# TaSCUD_ver03.net
KiCad netlist of a schematic drawn in EAGLE
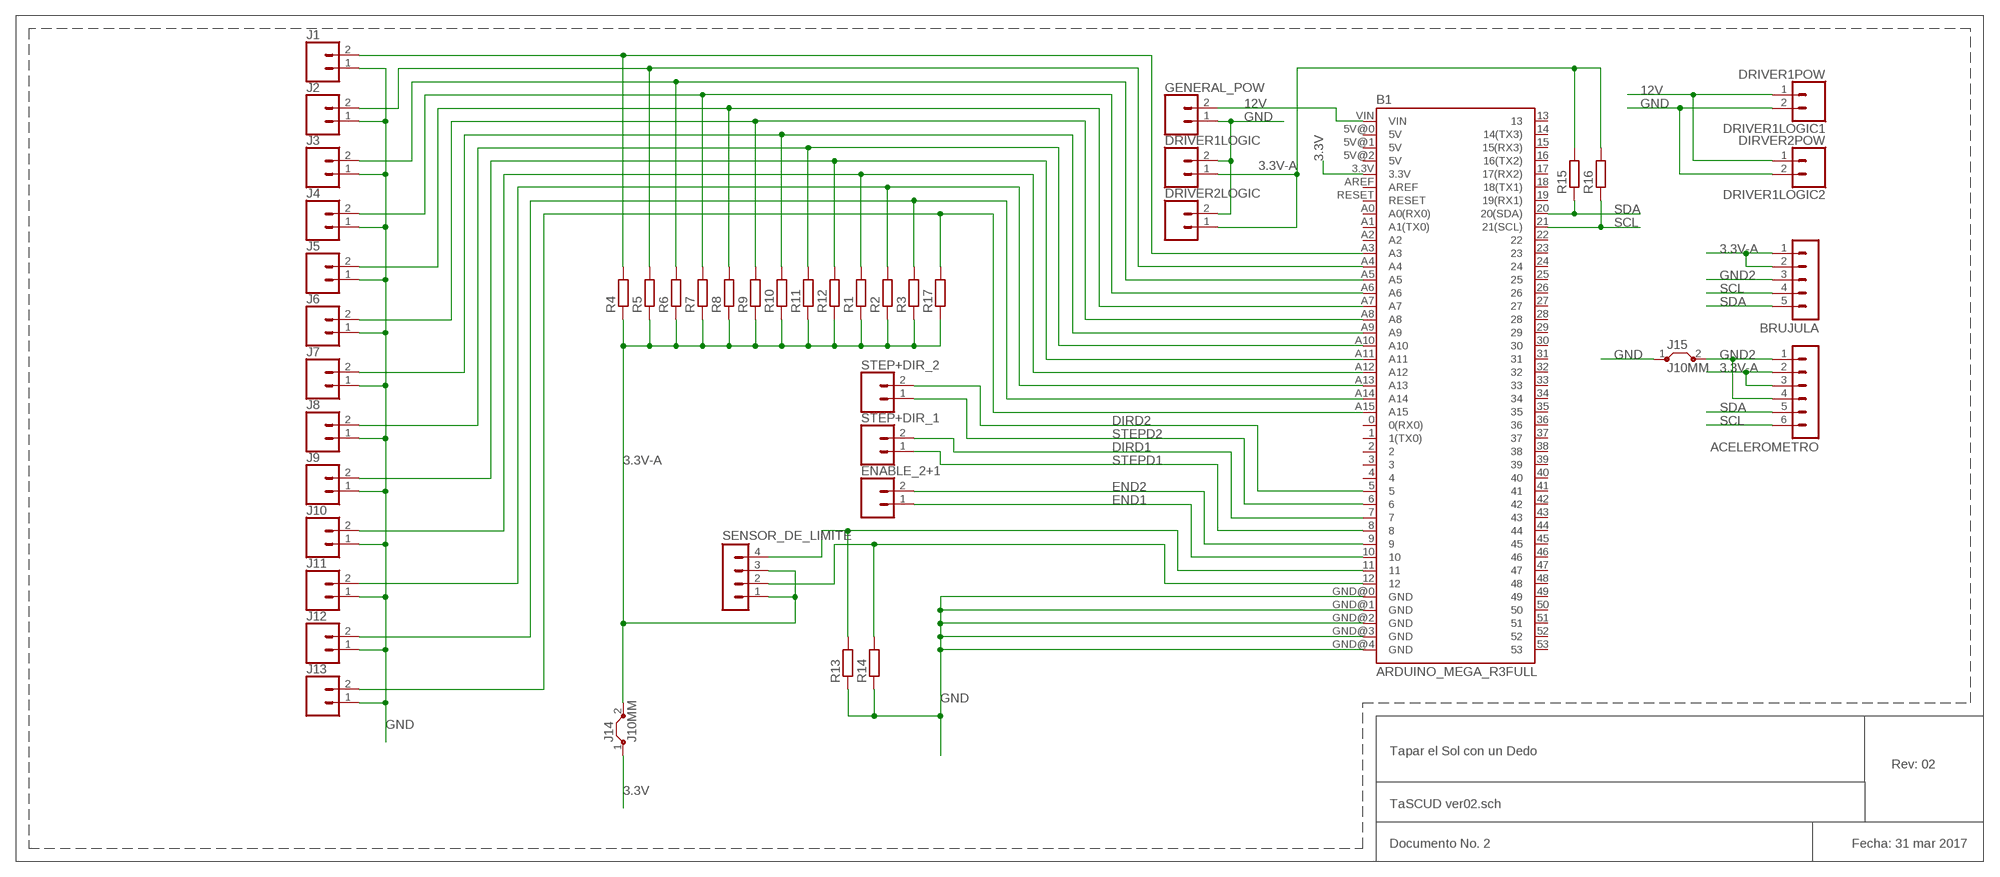
[diagram p0: schematic, sheet 1]

(export (version "E")
  (design (tool "Eeschema 10.0.6"))
  (components
    (comp (ref "ACELEROMETRO")
      (value "MA06-1")
      (footprint "eagle-import:MA06-1")
      (libsource (lib "eagle-import") (part "MA06-1"))
    )
    (comp (ref "B1")
      (value "ARDUINO_MEGA_R3FULL")
      (footprint "eagle-import:ARDUINO_MEGA")
      (libsource (lib "eagle-import") (part "ARDUINO_MEGA_R3FULL"))
    )
    (comp (ref "BRUJULA")
      (value "MA05-1")
      (footprint "eagle-import:MA05-1")
      (libsource (lib "eagle-import") (part "MA05-1"))
    )
    (comp (ref "DRIVER1LOGIC")
      (value "CONN_023.5MM-NO_SILK")
      (footprint "eagle-import:SCREWTERMINAL-3.5MM-2-NS")
      (libsource (lib "eagle-import") (part "CONN_023.5MM-NO_SILK"))
    )
    (comp (ref "DRIVER1LOGIC1")
      (value "DRIVER1POW")
      (footprint "eagle-import:SCREWTERMINAL-3.5MM-2-NS")
      (libsource (lib "eagle-import") (part "CONN_023.5MM-NO_SILK"))
    )
    (comp (ref "DRIVER1LOGIC2")
      (value "DIRVER2POW")
      (footprint "eagle-import:SCREWTERMINAL-3.5MM-2-NS")
      (libsource (lib "eagle-import") (part "CONN_023.5MM-NO_SILK"))
    )
    (comp (ref "DRIVER2LOGIC")
      (value "CONN_023.5MM-NO_SILK")
      (footprint "eagle-import:SCREWTERMINAL-3.5MM-2-NS")
      (libsource (lib "eagle-import") (part "CONN_023.5MM-NO_SILK"))
    )
    (comp (ref "ENABLE_2+1")
      (value "CONN_023.5MM-NO_SILK")
      (footprint "eagle-import:SCREWTERMINAL-3.5MM-2-NS")
      (libsource (lib "eagle-import") (part "CONN_023.5MM-NO_SILK"))
    )
    (comp (ref "GENERAL_POW")
      (value "CONN_023.5MM-NO_SILK")
      (footprint "eagle-import:SCREWTERMINAL-3.5MM-2-NS")
      (libsource (lib "eagle-import") (part "CONN_023.5MM-NO_SILK"))
    )
    (comp (ref "J1")
      (value "CONN_023.5MM-NO_SILK")
      (footprint "eagle-import:SCREWTERMINAL-3.5MM-2-NS")
      (libsource (lib "eagle-import") (part "CONN_023.5MM-NO_SILK"))
    )
    (comp (ref "J2")
      (value "CONN_023.5MM-NO_SILK")
      (footprint "eagle-import:SCREWTERMINAL-3.5MM-2-NS")
      (libsource (lib "eagle-import") (part "CONN_023.5MM-NO_SILK"))
    )
    (comp (ref "J3")
      (value "CONN_023.5MM-NO_SILK")
      (footprint "eagle-import:SCREWTERMINAL-3.5MM-2-NS")
      (libsource (lib "eagle-import") (part "CONN_023.5MM-NO_SILK"))
    )
    (comp (ref "J4")
      (value "CONN_023.5MM-NO_SILK")
      (footprint "eagle-import:SCREWTERMINAL-3.5MM-2-NS")
      (libsource (lib "eagle-import") (part "CONN_023.5MM-NO_SILK"))
    )
    (comp (ref "J5")
      (value "CONN_023.5MM-NO_SILK")
      (footprint "eagle-import:SCREWTERMINAL-3.5MM-2-NS")
      (libsource (lib "eagle-import") (part "CONN_023.5MM-NO_SILK"))
    )
    (comp (ref "J6")
      (value "CONN_023.5MM-NO_SILK")
      (footprint "eagle-import:SCREWTERMINAL-3.5MM-2-NS")
      (libsource (lib "eagle-import") (part "CONN_023.5MM-NO_SILK"))
    )
    (comp (ref "J7")
      (value "CONN_023.5MM-NO_SILK")
      (footprint "eagle-import:SCREWTERMINAL-3.5MM-2-NS")
      (libsource (lib "eagle-import") (part "CONN_023.5MM-NO_SILK"))
    )
    (comp (ref "J8")
      (value "CONN_023.5MM-NO_SILK")
      (footprint "eagle-import:SCREWTERMINAL-3.5MM-2-NS")
      (libsource (lib "eagle-import") (part "CONN_023.5MM-NO_SILK"))
    )
    (comp (ref "J9")
      (value "CONN_023.5MM-NO_SILK")
      (footprint "eagle-import:SCREWTERMINAL-3.5MM-2-NS")
      (libsource (lib "eagle-import") (part "CONN_023.5MM-NO_SILK"))
    )
    (comp (ref "J10")
      (value "CONN_023.5MM-NO_SILK")
      (footprint "eagle-import:SCREWTERMINAL-3.5MM-2-NS")
      (libsource (lib "eagle-import") (part "CONN_023.5MM-NO_SILK"))
    )
    (comp (ref "J11")
      (value "CONN_023.5MM-NO_SILK")
      (footprint "eagle-import:SCREWTERMINAL-3.5MM-2-NS")
      (libsource (lib "eagle-import") (part "CONN_023.5MM-NO_SILK"))
    )
    (comp (ref "J12")
      (value "CONN_023.5MM-NO_SILK")
      (footprint "eagle-import:SCREWTERMINAL-3.5MM-2-NS")
      (libsource (lib "eagle-import") (part "CONN_023.5MM-NO_SILK"))
    )
    (comp (ref "J13")
      (value "CONN_023.5MM-NO_SILK")
      (footprint "eagle-import:SCREWTERMINAL-3.5MM-2-NS")
      (libsource (lib "eagle-import") (part "CONN_023.5MM-NO_SILK"))
    )
    (comp (ref "J14")
      (value "J10MM")
      (footprint "eagle-import:10")
      (libsource (lib "eagle-import") (part "J10MM"))
    )
    (comp (ref "J15")
      (value "J10MM")
      (footprint "eagle-import:10")
      (libsource (lib "eagle-import") (part "J10MM"))
    )
    (comp (ref "R1")
      (value "R-EU_0204/7")
      (footprint "eagle-import:0204_7")
      (libsource (lib "eagle-import") (part "R-EU_0204/7"))
    )
    (comp (ref "R2")
      (value "R-EU_0204/7")
      (footprint "eagle-import:0204_7")
      (libsource (lib "eagle-import") (part "R-EU_0204/7"))
    )
    (comp (ref "R3")
      (value "R-EU_0204/7")
      (footprint "eagle-import:0204_7")
      (libsource (lib "eagle-import") (part "R-EU_0204/7"))
    )
    (comp (ref "R4")
      (value "R-EU_0204/7")
      (footprint "eagle-import:0204_7")
      (libsource (lib "eagle-import") (part "R-EU_0204/7"))
    )
    (comp (ref "R5")
      (value "R-EU_0204/7")
      (footprint "eagle-import:0204_7")
      (libsource (lib "eagle-import") (part "R-EU_0204/7"))
    )
    (comp (ref "R6")
      (value "R-EU_0204/7")
      (footprint "eagle-import:0204_7")
      (libsource (lib "eagle-import") (part "R-EU_0204/7"))
    )
    (comp (ref "R7")
      (value "R-EU_0204/7")
      (footprint "eagle-import:0204_7")
      (libsource (lib "eagle-import") (part "R-EU_0204/7"))
    )
    (comp (ref "R8")
      (value "R-EU_0204/7")
      (footprint "eagle-import:0204_7")
      (libsource (lib "eagle-import") (part "R-EU_0204/7"))
    )
    (comp (ref "R9")
      (value "R-EU_0204/7")
      (footprint "eagle-import:0204_7")
      (libsource (lib "eagle-import") (part "R-EU_0204/7"))
    )
    (comp (ref "R10")
      (value "R-EU_0204/7")
      (footprint "eagle-import:0204_7")
      (libsource (lib "eagle-import") (part "R-EU_0204/7"))
    )
    (comp (ref "R11")
      (value "R-EU_0204/7")
      (footprint "eagle-import:0204_7")
      (libsource (lib "eagle-import") (part "R-EU_0204/7"))
    )
    (comp (ref "R12")
      (value "R-EU_0204/7")
      (footprint "eagle-import:0204_7")
      (libsource (lib "eagle-import") (part "R-EU_0204/7"))
    )
    (comp (ref "R13")
      (value "R-EU_0204/7")
      (footprint "eagle-import:0204_7")
      (libsource (lib "eagle-import") (part "R-EU_0204/7"))
    )
    (comp (ref "R14")
      (value "R-EU_0204/7")
      (footprint "eagle-import:0204_7")
      (libsource (lib "eagle-import") (part "R-EU_0204/7"))
    )
    (comp (ref "R15")
      (value "R-EU_0204/7")
      (footprint "eagle-import:0204_7")
      (libsource (lib "eagle-import") (part "R-EU_0204/7"))
    )
    (comp (ref "R16")
      (value "R-EU_0204/7")
      (footprint "eagle-import:0204_7")
      (libsource (lib "eagle-import") (part "R-EU_0204/7"))
    )
    (comp (ref "R17")
      (value "R-EU_0204/7")
      (footprint "eagle-import:0204_7")
      (libsource (lib "eagle-import") (part "R-EU_0204/7"))
    )
    (comp (ref "SENSOR_DE_LIMITE")
      (value "MA04-1")
      (footprint "eagle-import:MA04-1")
      (libsource (lib "eagle-import") (part "MA04-1"))
    )
    (comp (ref "STEP+DIR_1")
      (value "CONN_023.5MM-NO_SILK")
      (footprint "eagle-import:SCREWTERMINAL-3.5MM-2-NS")
      (libsource (lib "eagle-import") (part "CONN_023.5MM-NO_SILK"))
    )
    (comp (ref "STEP+DIR_2")
      (value "CONN_023.5MM-NO_SILK")
      (footprint "eagle-import:SCREWTERMINAL-3.5MM-2-NS")
      (libsource (lib "eagle-import") (part "CONN_023.5MM-NO_SILK"))
    )
  )
  (nets
    (net (code "1") (name "/3.3V") (class "Default")
      (node (ref "B1") (pin "3.3V") (pinfunction "3.3V_3.3V") (pintype "bidirectional"))
      (node (ref "J14") (pin "1") (pinfunction "1_1") (pintype "passive"))
    )
    (net (code "2") (name "/3.3V-A") (class "Default")
      (node (ref "ACELEROMETRO") (pin "2") (pinfunction "2_2") (pintype "passive"))
      (node (ref "ACELEROMETRO") (pin "3") (pinfunction "3_3") (pintype "passive"))
      (node (ref "BRUJULA") (pin "1") (pinfunction "1_1") (pintype "passive"))
      (node (ref "BRUJULA") (pin "2") (pinfunction "2_2") (pintype "passive"))
      (node (ref "DRIVER1LOGIC") (pin "1") (pinfunction "1_1") (pintype "passive"))
      (node (ref "DRIVER2LOGIC") (pin "1") (pinfunction "1_1") (pintype "passive"))
      (node (ref "J14") (pin "2") (pinfunction "2_2") (pintype "passive"))
      (node (ref "R1") (pin "1") (pinfunction "1_1") (pintype "passive"))
      (node (ref "R10") (pin "1") (pinfunction "1_1") (pintype "passive"))
      (node (ref "R11") (pin "1") (pinfunction "1_1") (pintype "passive"))
      (node (ref "R12") (pin "1") (pinfunction "1_1") (pintype "passive"))
      (node (ref "R15") (pin "2") (pinfunction "2_2") (pintype "passive"))
      (node (ref "R16") (pin "2") (pinfunction "2_2") (pintype "passive"))
      (node (ref "R17") (pin "1") (pinfunction "1_1") (pintype "passive"))
      (node (ref "R2") (pin "1") (pinfunction "1_1") (pintype "passive"))
      (node (ref "R3") (pin "1") (pinfunction "1_1") (pintype "passive"))
      (node (ref "R4") (pin "1") (pinfunction "1_1") (pintype "passive"))
      (node (ref "R5") (pin "1") (pinfunction "1_1") (pintype "passive"))
      (node (ref "R6") (pin "1") (pinfunction "1_1") (pintype "passive"))
      (node (ref "R7") (pin "1") (pinfunction "1_1") (pintype "passive"))
      (node (ref "R8") (pin "1") (pinfunction "1_1") (pintype "passive"))
      (node (ref "R9") (pin "1") (pinfunction "1_1") (pintype "passive"))
      (node (ref "SENSOR_DE_LIMITE") (pin "1") (pinfunction "1_1") (pintype "passive"))
      (node (ref "SENSOR_DE_LIMITE") (pin "3") (pinfunction "3_3") (pintype "passive"))
    )
    (net (code "3") (name "/12V") (class "Default")
      (node (ref "B1") (pin "VIN") (pinfunction "VIN_VIN") (pintype "bidirectional"))
      (node (ref "DRIVER1LOGIC1") (pin "1") (pinfunction "1_1") (pintype "passive"))
      (node (ref "DRIVER1LOGIC2") (pin "1") (pinfunction "1_1") (pintype "passive"))
      (node (ref "GENERAL_POW") (pin "2") (pinfunction "2_2") (pintype "passive"))
    )
    (net (code "4") (name "/DIRD1") (class "Default")
      (node (ref "B1") (pin "7") (pinfunction "7_7") (pintype "bidirectional"))
      (node (ref "STEP+DIR_1") (pin "2") (pinfunction "2_2") (pintype "passive"))
    )
    (net (code "5") (name "/DIRD2") (class "Default")
      (node (ref "B1") (pin "5") (pinfunction "5_5") (pintype "bidirectional"))
      (node (ref "STEP+DIR_2") (pin "2") (pinfunction "2_2") (pintype "passive"))
    )
    (net (code "6") (name "/END1") (class "Default")
      (node (ref "B1") (pin "10") (pinfunction "10_10") (pintype "bidirectional"))
      (node (ref "ENABLE_2+1") (pin "1") (pinfunction "1_1") (pintype "passive"))
    )
    (net (code "7") (name "/END2") (class "Default")
      (node (ref "B1") (pin "9") (pinfunction "9_9") (pintype "bidirectional"))
      (node (ref "ENABLE_2+1") (pin "2") (pinfunction "2_2") (pintype "passive"))
    )
    (net (code "8") (name "/GND") (class "Default")
      (node (ref "B1") (pin "GND@0") (pinfunction "GND_GND@0") (pintype "bidirectional"))
      (node (ref "B1") (pin "GND@1") (pinfunction "GND_GND@1") (pintype "bidirectional"))
      (node (ref "B1") (pin "GND@2") (pinfunction "GND_GND@2") (pintype "bidirectional"))
      (node (ref "B1") (pin "GND@3") (pinfunction "GND_GND@3") (pintype "bidirectional"))
      (node (ref "B1") (pin "GND@4") (pinfunction "GND_GND@4") (pintype "bidirectional"))
      (node (ref "DRIVER1LOGIC") (pin "2") (pinfunction "2_2") (pintype "passive"))
      (node (ref "DRIVER1LOGIC1") (pin "2") (pinfunction "2_2") (pintype "passive"))
      (node (ref "DRIVER1LOGIC2") (pin "2") (pinfunction "2_2") (pintype "passive"))
      (node (ref "DRIVER2LOGIC") (pin "2") (pinfunction "2_2") (pintype "passive"))
      (node (ref "GENERAL_POW") (pin "1") (pinfunction "1_1") (pintype "passive"))
      (node (ref "J1") (pin "1") (pinfunction "1_1") (pintype "passive"))
      (node (ref "J10") (pin "1") (pinfunction "1_1") (pintype "passive"))
      (node (ref "J11") (pin "1") (pinfunction "1_1") (pintype "passive"))
      (node (ref "J12") (pin "1") (pinfunction "1_1") (pintype "passive"))
      (node (ref "J13") (pin "1") (pinfunction "1_1") (pintype "passive"))
      (node (ref "J15") (pin "1") (pinfunction "1_1") (pintype "passive"))
      (node (ref "J2") (pin "1") (pinfunction "1_1") (pintype "passive"))
      (node (ref "J3") (pin "1") (pinfunction "1_1") (pintype "passive"))
      (node (ref "J4") (pin "1") (pinfunction "1_1") (pintype "passive"))
      (node (ref "J5") (pin "1") (pinfunction "1_1") (pintype "passive"))
      (node (ref "J6") (pin "1") (pinfunction "1_1") (pintype "passive"))
      (node (ref "J7") (pin "1") (pinfunction "1_1") (pintype "passive"))
      (node (ref "J8") (pin "1") (pinfunction "1_1") (pintype "passive"))
      (node (ref "J9") (pin "1") (pinfunction "1_1") (pintype "passive"))
      (node (ref "R13") (pin "1") (pinfunction "1_1") (pintype "passive"))
      (node (ref "R14") (pin "1") (pinfunction "1_1") (pintype "passive"))
    )
    (net (code "9") (name "/GND2") (class "Default")
      (node (ref "ACELEROMETRO") (pin "1") (pinfunction "1_1") (pintype "passive"))
      (node (ref "ACELEROMETRO") (pin "4") (pinfunction "4_4") (pintype "passive"))
      (node (ref "BRUJULA") (pin "3") (pinfunction "3_3") (pintype "passive"))
      (node (ref "J15") (pin "2") (pinfunction "2_2") (pintype "passive"))
    )
    (net (code "10") (name "/SCL") (class "Default")
      (node (ref "ACELEROMETRO") (pin "6") (pinfunction "6_6") (pintype "passive"))
      (node (ref "B1") (pin "21") (pinfunction "21(SCL)_21") (pintype "bidirectional"))
      (node (ref "BRUJULA") (pin "4") (pinfunction "4_4") (pintype "passive"))
      (node (ref "R16") (pin "1") (pinfunction "1_1") (pintype "passive"))
    )
    (net (code "11") (name "/SDA") (class "Default")
      (node (ref "ACELEROMETRO") (pin "5") (pinfunction "5_5") (pintype "passive"))
      (node (ref "B1") (pin "20") (pinfunction "20(SDA)_20") (pintype "bidirectional"))
      (node (ref "BRUJULA") (pin "5") (pinfunction "5_5") (pintype "passive"))
      (node (ref "R15") (pin "1") (pinfunction "1_1") (pintype "passive"))
    )
    (net (code "12") (name "/STEPD1") (class "Default")
      (node (ref "B1") (pin "8") (pinfunction "8_8") (pintype "bidirectional"))
      (node (ref "STEP+DIR_1") (pin "1") (pinfunction "1_1") (pintype "passive"))
    )
    (net (code "13") (name "/STEPD2") (class "Default")
      (node (ref "B1") (pin "6") (pinfunction "6_6") (pintype "bidirectional"))
      (node (ref "STEP+DIR_2") (pin "1") (pinfunction "1_1") (pintype "passive"))
    )
    (net (code "14") (name "Net-(B1-Pad11)") (class "Default")
      (node (ref "B1") (pin "11") (pinfunction "11_11") (pintype "bidirectional"))
      (node (ref "R13") (pin "2") (pinfunction "2_2") (pintype "passive"))
      (node (ref "SENSOR_DE_LIMITE") (pin "4") (pinfunction "4_4") (pintype "passive"))
    )
    (net (code "15") (name "Net-(B1-Pad12)") (class "Default")
      (node (ref "B1") (pin "12") (pinfunction "12_12") (pintype "bidirectional"))
      (node (ref "R14") (pin "2") (pinfunction "2_2") (pintype "passive"))
      (node (ref "SENSOR_DE_LIMITE") (pin "2") (pinfunction "2_2") (pintype "passive"))
    )
    (net (code "16") (name "Net-(B1-PadA3)") (class "Default")
      (node (ref "B1") (pin "A3") (pinfunction "A3_A3") (pintype "bidirectional"))
      (node (ref "J1") (pin "2") (pinfunction "2_2") (pintype "passive"))
      (node (ref "R4") (pin "2") (pinfunction "2_2") (pintype "passive"))
    )
    (net (code "17") (name "Net-(B1-PadA4)") (class "Default")
      (node (ref "B1") (pin "A4") (pinfunction "A4_A4") (pintype "bidirectional"))
      (node (ref "J2") (pin "2") (pinfunction "2_2") (pintype "passive"))
      (node (ref "R5") (pin "2") (pinfunction "2_2") (pintype "passive"))
    )
    (net (code "18") (name "Net-(B1-PadA5)") (class "Default")
      (node (ref "B1") (pin "A5") (pinfunction "A5_A5") (pintype "bidirectional"))
      (node (ref "J3") (pin "2") (pinfunction "2_2") (pintype "passive"))
      (node (ref "R6") (pin "2") (pinfunction "2_2") (pintype "passive"))
    )
    (net (code "19") (name "Net-(B1-PadA6)") (class "Default")
      (node (ref "B1") (pin "A6") (pinfunction "A6_A6") (pintype "bidirectional"))
      (node (ref "J4") (pin "2") (pinfunction "2_2") (pintype "passive"))
      (node (ref "R7") (pin "2") (pinfunction "2_2") (pintype "passive"))
    )
    (net (code "20") (name "Net-(B1-PadA7)") (class "Default")
      (node (ref "B1") (pin "A7") (pinfunction "A7_A7") (pintype "bidirectional"))
      (node (ref "J5") (pin "2") (pinfunction "2_2") (pintype "passive"))
      (node (ref "R8") (pin "2") (pinfunction "2_2") (pintype "passive"))
    )
    (net (code "21") (name "Net-(B1-PadA8)") (class "Default")
      (node (ref "B1") (pin "A8") (pinfunction "A8_A8") (pintype "bidirectional"))
      (node (ref "J6") (pin "2") (pinfunction "2_2") (pintype "passive"))
      (node (ref "R9") (pin "2") (pinfunction "2_2") (pintype "passive"))
    )
    (net (code "22") (name "Net-(B1-PadA9)") (class "Default")
      (node (ref "B1") (pin "A9") (pinfunction "A9_A9") (pintype "bidirectional"))
      (node (ref "J7") (pin "2") (pinfunction "2_2") (pintype "passive"))
      (node (ref "R10") (pin "2") (pinfunction "2_2") (pintype "passive"))
    )
    (net (code "23") (name "Net-(B1-PadA10)") (class "Default")
      (node (ref "B1") (pin "A10") (pinfunction "A10_A10") (pintype "bidirectional"))
      (node (ref "J8") (pin "2") (pinfunction "2_2") (pintype "passive"))
      (node (ref "R11") (pin "2") (pinfunction "2_2") (pintype "passive"))
    )
    (net (code "24") (name "Net-(B1-PadA11)") (class "Default")
      (node (ref "B1") (pin "A11") (pinfunction "A11_A11") (pintype "bidirectional"))
      (node (ref "J9") (pin "2") (pinfunction "2_2") (pintype "passive"))
      (node (ref "R12") (pin "2") (pinfunction "2_2") (pintype "passive"))
    )
    (net (code "25") (name "Net-(B1-PadA12)") (class "Default")
      (node (ref "B1") (pin "A12") (pinfunction "A12_A12") (pintype "bidirectional"))
      (node (ref "J10") (pin "2") (pinfunction "2_2") (pintype "passive"))
      (node (ref "R1") (pin "2") (pinfunction "2_2") (pintype "passive"))
    )
    (net (code "26") (name "Net-(B1-PadA13)") (class "Default")
      (node (ref "B1") (pin "A13") (pinfunction "A13_A13") (pintype "bidirectional"))
      (node (ref "J11") (pin "2") (pinfunction "2_2") (pintype "passive"))
      (node (ref "R2") (pin "2") (pinfunction "2_2") (pintype "passive"))
    )
    (net (code "27") (name "Net-(B1-PadA14)") (class "Default")
      (node (ref "B1") (pin "A14") (pinfunction "A14_A14") (pintype "bidirectional"))
      (node (ref "J12") (pin "2") (pinfunction "2_2") (pintype "passive"))
      (node (ref "R3") (pin "2") (pinfunction "2_2") (pintype "passive"))
    )
    (net (code "28") (name "Net-(B1-PadA15)") (class "Default")
      (node (ref "B1") (pin "A15") (pinfunction "A15_A15") (pintype "bidirectional"))
      (node (ref "J13") (pin "2") (pinfunction "2_2") (pintype "passive"))
      (node (ref "R17") (pin "2") (pinfunction "2_2") (pintype "passive"))
    )
    (net (code "29") (name "unconnected-(B1-0(RX0)-Pad0)") (class "Default")
      (node (ref "B1") (pin "0") (pinfunction "0(RX0)_0") (pintype "bidirectional"))
    )
    (net (code "30") (name "unconnected-(B1-1(TX0)-Pad1)") (class "Default")
      (node (ref "B1") (pin "1") (pinfunction "1(TX0)_1") (pintype "bidirectional"))
    )
    (net (code "31") (name "unconnected-(B1-5V-Pad5V@0)") (class "Default")
      (node (ref "B1") (pin "5V@0") (pinfunction "5V_5V@0") (pintype "bidirectional"))
    )
    (net (code "32") (name "unconnected-(B1-5V-Pad5V@1)") (class "Default")
      (node (ref "B1") (pin "5V@1") (pinfunction "5V_5V@1") (pintype "bidirectional"))
    )
    (net (code "33") (name "unconnected-(B1-5V-Pad5V@2)") (class "Default")
      (node (ref "B1") (pin "5V@2") (pinfunction "5V_5V@2") (pintype "bidirectional"))
    )
    (net (code "34") (name "unconnected-(B1-14(TX3)-Pad14)") (class "Default")
      (node (ref "B1") (pin "14") (pinfunction "14(TX3)_14") (pintype "bidirectional"))
    )
    (net (code "35") (name "unconnected-(B1-15(RX3)-Pad15)") (class "Default")
      (node (ref "B1") (pin "15") (pinfunction "15(RX3)_15") (pintype "bidirectional"))
    )
    (net (code "36") (name "unconnected-(B1-16(TX2)-Pad16)") (class "Default")
      (node (ref "B1") (pin "16") (pinfunction "16(TX2)_16") (pintype "bidirectional"))
    )
    (net (code "37") (name "unconnected-(B1-17(RX2)-Pad17)") (class "Default")
      (node (ref "B1") (pin "17") (pinfunction "17(RX2)_17") (pintype "bidirectional"))
    )
    (net (code "38") (name "unconnected-(B1-18(TX1)-Pad18)") (class "Default")
      (node (ref "B1") (pin "18") (pinfunction "18(TX1)_18") (pintype "bidirectional"))
    )
    (net (code "39") (name "unconnected-(B1-19(RX1)-Pad19)") (class "Default")
      (node (ref "B1") (pin "19") (pinfunction "19(RX1)_19") (pintype "bidirectional"))
    )
    (net (code "40") (name "unconnected-(B1-A0(RX0)-PadA0)") (class "Default")
      (node (ref "B1") (pin "A0") (pinfunction "A0(RX0)_A0") (pintype "bidirectional"))
    )
    (net (code "41") (name "unconnected-(B1-A1(TX0)-PadA1)") (class "Default")
      (node (ref "B1") (pin "A1") (pinfunction "A1(TX0)_A1") (pintype "bidirectional"))
    )
    (net (code "42") (name "unconnected-(B1-Pad2)") (class "Default")
      (node (ref "B1") (pin "2") (pinfunction "2_2") (pintype "bidirectional"))
    )
    (net (code "43") (name "unconnected-(B1-Pad3)") (class "Default")
      (node (ref "B1") (pin "3") (pinfunction "3_3") (pintype "bidirectional"))
    )
    (net (code "44") (name "unconnected-(B1-Pad4)") (class "Default")
      (node (ref "B1") (pin "4") (pinfunction "4_4") (pintype "bidirectional"))
    )
    (net (code "45") (name "unconnected-(B1-Pad13)") (class "Default")
      (node (ref "B1") (pin "13") (pinfunction "13_13") (pintype "bidirectional"))
    )
    (net (code "46") (name "unconnected-(B1-Pad22)") (class "Default")
      (node (ref "B1") (pin "22") (pinfunction "22_22") (pintype "bidirectional"))
    )
    (net (code "47") (name "unconnected-(B1-Pad23)") (class "Default")
      (node (ref "B1") (pin "23") (pinfunction "23_23") (pintype "bidirectional"))
    )
    (net (code "48") (name "unconnected-(B1-Pad24)") (class "Default")
      (node (ref "B1") (pin "24") (pinfunction "24_24") (pintype "bidirectional"))
    )
    (net (code "49") (name "unconnected-(B1-Pad25)") (class "Default")
      (node (ref "B1") (pin "25") (pinfunction "25_25") (pintype "bidirectional"))
    )
    (net (code "50") (name "unconnected-(B1-Pad26)") (class "Default")
      (node (ref "B1") (pin "26") (pinfunction "26_26") (pintype "bidirectional"))
    )
    (net (code "51") (name "unconnected-(B1-Pad27)") (class "Default")
      (node (ref "B1") (pin "27") (pinfunction "27_27") (pintype "bidirectional"))
    )
    (net (code "52") (name "unconnected-(B1-Pad28)") (class "Default")
      (node (ref "B1") (pin "28") (pinfunction "28_28") (pintype "bidirectional"))
    )
    (net (code "53") (name "unconnected-(B1-Pad29)") (class "Default")
      (node (ref "B1") (pin "29") (pinfunction "29_29") (pintype "bidirectional"))
    )
    (net (code "54") (name "unconnected-(B1-Pad30)") (class "Default")
      (node (ref "B1") (pin "30") (pinfunction "30_30") (pintype "bidirectional"))
    )
    (net (code "55") (name "unconnected-(B1-Pad31)") (class "Default")
      (node (ref "B1") (pin "31") (pinfunction "31_31") (pintype "bidirectional"))
    )
    (net (code "56") (name "unconnected-(B1-Pad32)") (class "Default")
      (node (ref "B1") (pin "32") (pinfunction "32_32") (pintype "bidirectional"))
    )
    (net (code "57") (name "unconnected-(B1-Pad33)") (class "Default")
      (node (ref "B1") (pin "33") (pinfunction "33_33") (pintype "bidirectional"))
    )
    (net (code "58") (name "unconnected-(B1-Pad34)") (class "Default")
      (node (ref "B1") (pin "34") (pinfunction "34_34") (pintype "bidirectional"))
    )
    (net (code "59") (name "unconnected-(B1-Pad35)") (class "Default")
      (node (ref "B1") (pin "35") (pinfunction "35_35") (pintype "bidirectional"))
    )
    (net (code "60") (name "unconnected-(B1-Pad36)") (class "Default")
      (node (ref "B1") (pin "36") (pinfunction "36_36") (pintype "bidirectional"))
    )
    (net (code "61") (name "unconnected-(B1-Pad37)") (class "Default")
      (node (ref "B1") (pin "37") (pinfunction "37_37") (pintype "bidirectional"))
    )
    (net (code "62") (name "unconnected-(B1-Pad38)") (class "Default")
      (node (ref "B1") (pin "38") (pinfunction "38_38") (pintype "bidirectional"))
    )
    (net (code "63") (name "unconnected-(B1-Pad39)") (class "Default")
      (node (ref "B1") (pin "39") (pinfunction "39_39") (pintype "bidirectional"))
    )
    (net (code "64") (name "unconnected-(B1-Pad40)") (class "Default")
      (node (ref "B1") (pin "40") (pinfunction "40_40") (pintype "bidirectional"))
    )
    (net (code "65") (name "unconnected-(B1-Pad41)") (class "Default")
      (node (ref "B1") (pin "41") (pinfunction "41_41") (pintype "bidirectional"))
    )
    (net (code "66") (name "unconnected-(B1-Pad42)") (class "Default")
      (node (ref "B1") (pin "42") (pinfunction "42_42") (pintype "bidirectional"))
    )
    (net (code "67") (name "unconnected-(B1-Pad43)") (class "Default")
      (node (ref "B1") (pin "43") (pinfunction "43_43") (pintype "bidirectional"))
    )
    (net (code "68") (name "unconnected-(B1-Pad44)") (class "Default")
      (node (ref "B1") (pin "44") (pinfunction "44_44") (pintype "bidirectional"))
    )
    (net (code "69") (name "unconnected-(B1-Pad45)") (class "Default")
      (node (ref "B1") (pin "45") (pinfunction "45_45") (pintype "bidirectional"))
    )
    (net (code "70") (name "unconnected-(B1-Pad46)") (class "Default")
      (node (ref "B1") (pin "46") (pinfunction "46_46") (pintype "bidirectional"))
    )
    (net (code "71") (name "unconnected-(B1-Pad47)") (class "Default")
      (node (ref "B1") (pin "47") (pinfunction "47_47") (pintype "bidirectional"))
    )
    (net (code "72") (name "unconnected-(B1-Pad48)") (class "Default")
      (node (ref "B1") (pin "48") (pinfunction "48_48") (pintype "bidirectional"))
    )
    (net (code "73") (name "unconnected-(B1-Pad49)") (class "Default")
      (node (ref "B1") (pin "49") (pinfunction "49_49") (pintype "bidirectional"))
    )
    (net (code "74") (name "unconnected-(B1-Pad50)") (class "Default")
      (node (ref "B1") (pin "50") (pinfunction "50_50") (pintype "bidirectional"))
    )
    (net (code "75") (name "unconnected-(B1-Pad51)") (class "Default")
      (node (ref "B1") (pin "51") (pinfunction "51_51") (pintype "bidirectional"))
    )
    (net (code "76") (name "unconnected-(B1-Pad52)") (class "Default")
      (node (ref "B1") (pin "52") (pinfunction "52_52") (pintype "bidirectional"))
    )
    (net (code "77") (name "unconnected-(B1-Pad53)") (class "Default")
      (node (ref "B1") (pin "53") (pinfunction "53_53") (pintype "bidirectional"))
    )
    (net (code "78") (name "unconnected-(B1-PadA2)") (class "Default")
      (node (ref "B1") (pin "A2") (pinfunction "A2_A2") (pintype "bidirectional"))
    )
    (net (code "79") (name "unconnected-(B1-PadAREF)") (class "Default")
      (node (ref "B1") (pin "AREF") (pinfunction "AREF_AREF") (pintype "bidirectional"))
    )
    (net (code "80") (name "unconnected-(B1-PadRESET)") (class "Default")
      (node (ref "B1") (pin "RESET") (pinfunction "RESET_RESET") (pintype "bidirectional"))
    )
  )
)
